# Boost_Converter.net
KiCad netlist of a schematic drawn in Altium Designer
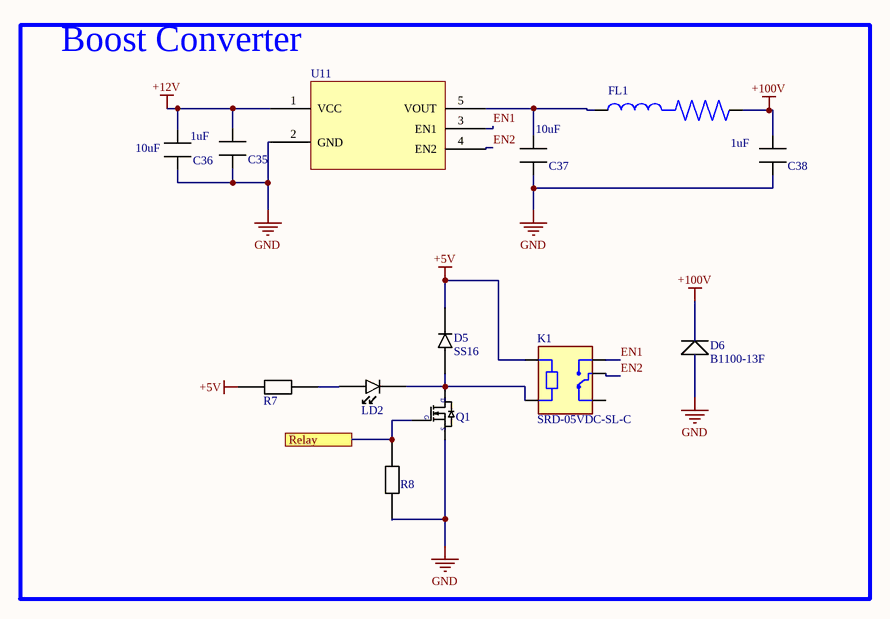
[diagram p0: Boost Converter.SchDoc]

(export (version "E")
  (design (tool "Eeschema 10.0.6"))
  (components
    (comp (ref "C35")
      (value "1uF")
      (footprint "CAP_1206")
      (description "CAP_1206")
      (fields (field (name "VAL") "1uF"))
      (libsource (lib "Passives") (part "CAP_1206"))
    )
    (comp (ref "C36")
      (value "10uF")
      (footprint "CAP_0805")
      (description "CAP_0805")
      (fields (field (name "VAL") "10uF"))
      (libsource (lib "Passives") (part "CAP_0805"))
    )
    (comp (ref "C37")
      (value "10uF")
      (footprint "CAP_1206")
      (description "CAP_1206")
      (fields (field (name "VAL") "10uF"))
      (libsource (lib "Passives") (part "CAP_1206"))
    )
    (comp (ref "C38")
      (value "1uF")
      (footprint "CAP_1206")
      (description "CAP_1206")
      (fields (field (name "VAL") "1uF"))
      (libsource (lib "Passives") (part "CAP_1206"))
    )
    (comp (ref "D5")
      (value "SS16")
      (footprint "DO-214AC")
      (description "Independent 60V 700mV@1A 1A SMA(DO-214AC) Single Diodes RoHS")
      (libsource (lib "Diodes") (part "SS16"))
    )
    (comp (ref "D6")
      (value "B1100-13F")
      (footprint "DIOM5226X230N")
      (libsource (lib "Diodes") (part "B1100-13F"))
    )
    (comp (ref "FL1")
      (value "~")
      (footprint "BEAD1206S601A40T")
      (fields (field (name "MF") "Murata") (field (name "MP") "BLM03EB500SZ1D"))
      (libsource (lib "Passives") (part "BEAD1206S601A40T"))
    )
    (comp (ref "K1")
      (value "SRD-05VDC-SL-C")
      (footprint "RELAY_SRD-05VDC-SL-C")
      (fields (field (name "MF") "Songle Relay"))
      (libsource (lib "IC_Power") (part "SRD-05VDC-SL-C"))
    )
    (comp (ref "LD2")
      (value "LED_0805")
      (footprint "LED_0805")
      (libsource (lib "Passives") (part "LED_0805"))
    )
    (comp (ref "Q1")
      (value "DMN3404L-7")
      (footprint "SOT23-3")
      (description "N-Channel 30V 5.8A 1.4W Surface Mount SOT-23")
      (libsource (lib "Transistors_Relays") (part "DMN3404L-7"))
    )
    (comp (ref "R7")
      (value "330")
      (footprint "RES_0805")
      (description "RES_0805")
      (libsource (lib "Passives") (part "RES_0805"))
    )
    (comp (ref "R8")
      (value "4.7k")
      (footprint "RES_0805")
      (description "RES_0805")
      (libsource (lib "Passives") (part "RES_0805"))
    )
    (comp (ref "U11")
      (value "Boost_Conv_Module")
      (footprint "Boost_Converter")
      (libsource (lib "IC_Power") (part "Boost_Converter"))
    )
  )
  (nets
    (net (code "1") (name "+5V") (class "Default")
      (node (ref "D5") (pin "1") (pinfunction "1_1") (pintype "passive"))
      (node (ref "K1") (pin "A1") (pinfunction "A1_A1") (pintype "passive"))
      (node (ref "R7") (pin "2") (pinfunction "2_2") (pintype "passive"))
    )
    (net (code "2") (name "+12V") (class "Default")
      (node (ref "C35") (pin "2") (pinfunction "2_2") (pintype "passive"))
      (node (ref "C36") (pin "2") (pinfunction "2_2") (pintype "passive"))
      (node (ref "U11") (pin "1") (pinfunction "VCC_1") (pintype "passive"))
    )
    (net (code "3") (name "+100V") (class "Default")
      (node (ref "C38") (pin "2") (pinfunction "2_2") (pintype "passive"))
      (node (ref "D6") (pin "1") (pinfunction "-_1") (pintype "passive"))
      (node (ref "FL1") (pin "2") (pinfunction "2_2") (pintype "passive"))
    )
    (net (code "4") (name "/EN1") (class "Default")
      (node (ref "K1") (pin "NO") (pinfunction "NO_NO") (pintype "passive"))
      (node (ref "U11") (pin "3") (pinfunction "EN1_3") (pintype "passive"))
    )
    (net (code "5") (name "/EN2") (class "Default")
      (node (ref "K1") (pin "COM") (pinfunction "COM_COM") (pintype "passive"))
      (node (ref "U11") (pin "4") (pinfunction "EN2_4") (pintype "passive"))
    )
    (net (code "6") (name "/Relay") (class "Default")
      (node (ref "Q1") (pin "1") (pinfunction "1_1") (pintype "passive"))
      (node (ref "R8") (pin "2") (pinfunction "2_2") (pintype "passive"))
    )
    (net (code "7") (name "GND") (class "Default")
      (node (ref "C35") (pin "1") (pinfunction "1_1") (pintype "passive"))
      (node (ref "C36") (pin "1") (pinfunction "1_1") (pintype "passive"))
      (node (ref "C37") (pin "1") (pinfunction "1_1") (pintype "passive"))
      (node (ref "C38") (pin "1") (pinfunction "1_1") (pintype "passive"))
      (node (ref "D6") (pin "2") (pinfunction "+_2") (pintype "passive"))
      (node (ref "Q1") (pin "2") (pinfunction "2_2") (pintype "passive"))
      (node (ref "R8") (pin "1") (pinfunction "1_1") (pintype "passive"))
      (node (ref "U11") (pin "2") (pinfunction "GND_2") (pintype "passive"))
    )
    (net (code "8") (name "Net-(D5-Pad2)") (class "Default")
      (node (ref "D5") (pin "2") (pinfunction "2_2") (pintype "passive"))
      (node (ref "K1") (pin "A2") (pinfunction "A2_A2") (pintype "passive"))
      (node (ref "LD2") (pin "1") (pinfunction "1_1") (pintype "passive"))
      (node (ref "Q1") (pin "3") (pinfunction "3_3") (pintype "passive"))
    )
    (net (code "9") (name "Net-(LD2-Pad2)") (class "Default")
      (node (ref "LD2") (pin "2") (pinfunction "2_2") (pintype "passive"))
      (node (ref "R7") (pin "1") (pinfunction "1_1") (pintype "passive"))
    )
    (net (code "10") (name "Net-(U11-VOUT)") (class "Default")
      (node (ref "C37") (pin "2") (pinfunction "2_2") (pintype "passive"))
      (node (ref "FL1") (pin "1") (pinfunction "1_1") (pintype "passive"))
      (node (ref "U11") (pin "5") (pinfunction "VOUT_5") (pintype "passive"))
    )
    (net (code "11") (name "unconnected-(K1-PadNC)") (class "Default")
      (node (ref "K1") (pin "NC") (pinfunction "NC_NC") (pintype "passive"))
    )
  )
)
